# TopLevel.net
KiCad netlist of a schematic drawn in Altium Designer
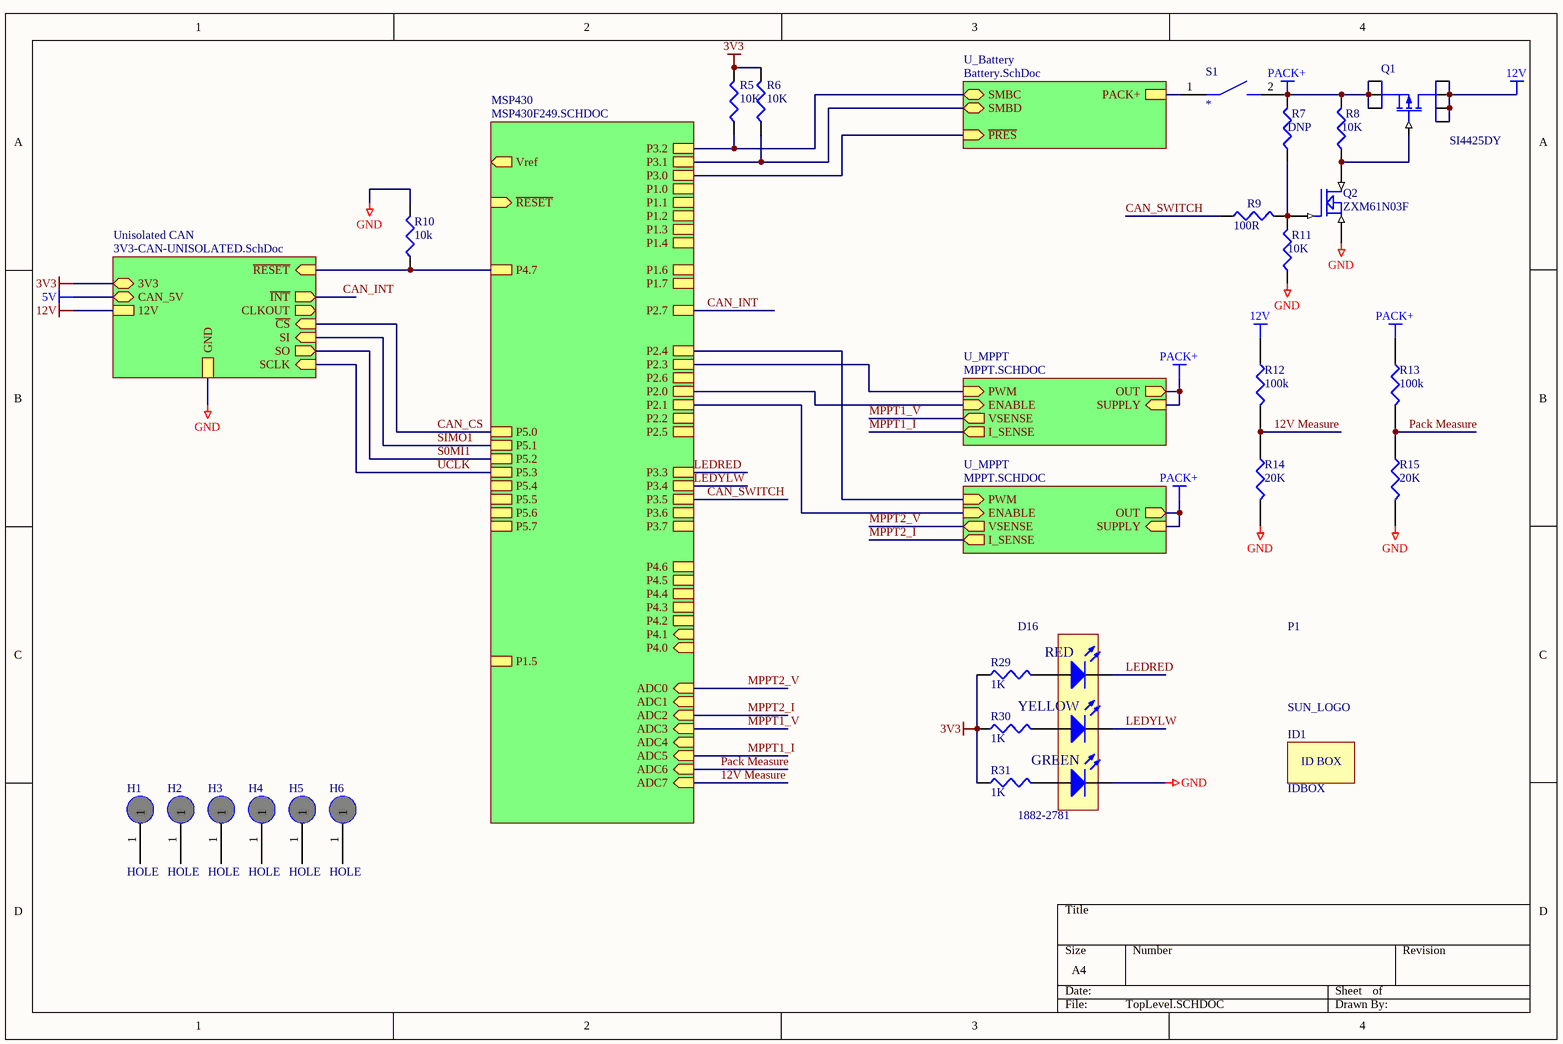
[diagram p0: TopLevel.SCHDOC]

(export (version "E")
  (design (tool "Eeschema 10.0.6"))
  (components
    (comp (ref "D16")
      (value "1882-2781")
      (footprint "LED_TRILEVEL")
      (description "Three level LED")
      (libsource (lib "RCLDQ") (part "LED-TRILEVEL"))
    )
    (comp (ref "H1")
      (value "HOLE")
      (footprint "M3")
      (description "Hole")
      (libsource (lib "Miscellaneous") (part "HOLE"))
    )
    (comp (ref "H2")
      (value "HOLE")
      (footprint "M3")
      (description "Hole")
      (libsource (lib "Miscellaneous") (part "HOLE"))
    )
    (comp (ref "H3")
      (value "HOLE")
      (footprint "M3")
      (description "Hole")
      (libsource (lib "Miscellaneous") (part "HOLE"))
    )
    (comp (ref "H4")
      (value "HOLE")
      (footprint "M3")
      (description "Hole")
      (libsource (lib "Miscellaneous") (part "HOLE"))
    )
    (comp (ref "H5")
      (value "HOLE")
      (footprint "M3")
      (description "Hole")
      (libsource (lib "Miscellaneous") (part "HOLE"))
    )
    (comp (ref "H6")
      (value "HOLE")
      (footprint "M3")
      (description "Hole")
      (libsource (lib "Miscellaneous") (part "HOLE"))
    )
    (comp (ref "ID1") (value "IDBOX") (footprint "IDBOX") (libsource (lib "Miscellaneous") (part "IDBOX")))
    (comp (ref "P1")
      (value "SUN_LOGO")
      (footprint "SUNSWIFTLOGO")
      (libsource (lib "Miscellaneous") (part "SUN_LOGO"))
    )
    (comp (ref "Q1")
      (value "SI4425DY")
      (footprint "SO8")
      (description "SI4425DY P Channel Mosfet")
      (libsource (lib "RCLDQ") (part "SI4425DY"))
    )
    (comp (ref "Q2")
      (value "ZXM61N03F")
      (footprint "SOT23(3)")
      (description "1.7A, 20V N-Channel Enhancement mode FET")
      (libsource (lib "RCLDQ") (part "ZXM61N02F"))
    )
    (comp (ref "R5")
      (value "10K")
      (footprint "0603")
      (description "Resistor")
      (libsource (lib "RCLDQ") (part "RES1"))
    )
    (comp (ref "R6")
      (value "10K")
      (footprint "0603")
      (description "Resistor")
      (libsource (lib "RCLDQ") (part "RES1"))
    )
    (comp (ref "R7")
      (value "DNP")
      (footprint "0603")
      (description "Resistor")
      (libsource (lib "*") (part "RES1"))
    )
    (comp (ref "R8")
      (value "10K")
      (footprint "0603")
      (description "Resistor")
      (libsource (lib "*") (part "RES1"))
    )
    (comp (ref "R9") (value "100R") (footprint "0603") (libsource (lib "RCLDQ") (part "RES1")))
    (comp (ref "R10")
      (value "10k")
      (footprint "0603")
      (description "Resistor")
      (libsource (lib "SunswiftLib20030312RR") (part "RES1"))
    )
    (comp (ref "R11")
      (value "10K")
      (footprint "0603")
      (description "Resistor")
      (libsource (lib "*") (part "RES1"))
    )
    (comp (ref "R12") (value "100k") (footprint "1206") (libsource (lib "") (part "RES1_1")))
    (comp (ref "R13") (value "100k") (footprint "1206") (libsource (lib "") (part "RES1_1")))
    (comp (ref "R14") (value "20K") (footprint "1206") (libsource (lib "") (part "RES1_1")))
    (comp (ref "R15") (value "20K") (footprint "1206") (libsource (lib "") (part "RES1_1")))
    (comp (ref "R29")
      (value "1K")
      (footprint "0603")
      (description "Resistor")
      (libsource (lib "RCLDQ") (part "RES1"))
    )
    (comp (ref "R30")
      (value "1K")
      (footprint "0603")
      (description "Resistor")
      (libsource (lib "RCLDQ") (part "RES1"))
    )
    (comp (ref "R31")
      (value "1K")
      (footprint "0603")
      (description "Resistor")
      (libsource (lib "RCLDQ") (part "RES1"))
    )
    (comp (ref "S1") (value "*") (libsource (lib "Miscellaneous") (part "SWITCH")))
  )
  (nets
    (net (code "1") (name "/12V Measure") (class "Default")
      (node (ref "R12") (pin "2") (pinfunction "2_2") (pintype "passive"))
      (node (ref "R14") (pin "1") (pinfunction "1_1") (pintype "passive"))
    )
    (net (code "6") (name "/CAN_SWITCH") (class "Default")
      (node (ref "R9") (pin "1") (pinfunction "1_1") (pintype "passive"))
    )
    (net (code "10") (name "/LEDRED") (class "Default")
      (node (ref "D16") (pin "3") (pinfunction "K_3") (pintype "passive"))
    )
    (net (code "11") (name "/LEDYLW") (class "Default")
      (node (ref "D16") (pin "2") (pinfunction "K_2") (pintype "passive"))
    )
    (net (code "30") (name "/P3.1") (class "Default")
      (node (ref "R6") (pin "1") (pinfunction "1_1") (pintype "passive"))
    )
    (net (code "31") (name "/P3.2") (class "Default")
      (node (ref "R5") (pin "1") (pinfunction "1_1") (pintype "passive"))
    )
    (net (code "41") (name "/P4.7") (class "Default")
      (node (ref "R10") (pin "1") (pinfunction "1_1") (pintype "passive"))
    )
    (net (code "46") (name "/PACK+") (class "Default")
      (node (ref "S1") (pin "1") (pinfunction "1_1") (pintype "passive"))
    )
    (net (code "47") (name "/Pack Measure") (class "Default")
      (node (ref "R13") (pin "2") (pinfunction "2_2") (pintype "passive"))
      (node (ref "R15") (pin "1") (pinfunction "1_1") (pintype "passive"))
    )
    (net (code "53") (name "3V3") (class "Default")
      (node (ref "R29") (pin "1") (pinfunction "1_1") (pintype "passive"))
      (node (ref "R30") (pin "1") (pinfunction "1_1") (pintype "passive"))
      (node (ref "R31") (pin "1") (pinfunction "1_1") (pintype "passive"))
      (node (ref "R5") (pin "2") (pinfunction "2_2") (pintype "passive"))
      (node (ref "R6") (pin "2") (pinfunction "2_2") (pintype "passive"))
    )
    (net (code "55") (name "12V") (class "Default")
      (node (ref "Q1") (pin "5") (pinfunction "D_5") (pintype "bidirectional"))
      (node (ref "Q1") (pin "6") (pinfunction "D_6") (pintype "bidirectional"))
      (node (ref "Q1") (pin "7") (pinfunction "D_7") (pintype "bidirectional"))
      (node (ref "Q1") (pin "8") (pinfunction "D_8") (pintype "bidirectional"))
      (node (ref "R12") (pin "1") (pinfunction "1_1") (pintype "passive"))
    )
    (net (code "56") (name "GND") (class "Default")
      (node (ref "D16") (pin "1") (pinfunction "K_1") (pintype "passive"))
      (node (ref "Q2") (pin "2") (pinfunction "S_2") (pintype "input"))
      (node (ref "R10") (pin "2") (pinfunction "2_2") (pintype "passive"))
      (node (ref "R11") (pin "1") (pinfunction "1_1") (pintype "passive"))
      (node (ref "R14") (pin "2") (pinfunction "2_2") (pintype "passive"))
      (node (ref "R15") (pin "2") (pinfunction "2_2") (pintype "passive"))
    )
    (net (code "57") (name "Net-(D16-A-Pad4)") (class "Default")
      (node (ref "D16") (pin "4") (pinfunction "A_4") (pintype "passive"))
      (node (ref "R29") (pin "2") (pinfunction "2_2") (pintype "passive"))
    )
    (net (code "58") (name "Net-(D16-A-Pad5)") (class "Default")
      (node (ref "D16") (pin "5") (pinfunction "A_5") (pintype "passive"))
      (node (ref "R30") (pin "2") (pinfunction "2_2") (pintype "passive"))
    )
    (net (code "59") (name "Net-(D16-A-Pad6)") (class "Default")
      (node (ref "D16") (pin "6") (pinfunction "A_6") (pintype "passive"))
      (node (ref "R31") (pin "2") (pinfunction "2_2") (pintype "passive"))
    )
    (net (code "60") (name "Net-(Q1-G)") (class "Default")
      (node (ref "Q1") (pin "4") (pinfunction "G_4") (pintype "input"))
      (node (ref "Q2") (pin "3") (pinfunction "D_3") (pintype "input"))
      (node (ref "R8") (pin "1") (pinfunction "1_1") (pintype "passive"))
    )
    (net (code "61") (name "Net-(Q2-G)") (class "Default")
      (node (ref "Q2") (pin "1") (pinfunction "G_1") (pintype "input"))
      (node (ref "R11") (pin "2") (pinfunction "2_2") (pintype "passive"))
      (node (ref "R7") (pin "1") (pinfunction "1_1") (pintype "passive"))
      (node (ref "R9") (pin "2") (pinfunction "2_2") (pintype "passive"))
    )
    (net (code "62") (name "PACK+") (class "Default")
      (node (ref "Q1") (pin "1") (pinfunction "S_1") (pintype "bidirectional"))
      (node (ref "Q1") (pin "2") (pinfunction "S_2") (pintype "bidirectional"))
      (node (ref "Q1") (pin "3") (pinfunction "S_3") (pintype "bidirectional"))
      (node (ref "R13") (pin "1") (pinfunction "1_1") (pintype "passive"))
      (node (ref "R7") (pin "2") (pinfunction "2_2") (pintype "passive"))
      (node (ref "R8") (pin "2") (pinfunction "2_2") (pintype "passive"))
      (node (ref "S1") (pin "2") (pinfunction "2_2") (pintype "passive"))
    )
    (net (code "63") (name "unconnected-(H1-Pad1)") (class "Default")
      (node (ref "H1") (pin "1") (pinfunction "1_1") (pintype "passive"))
    )
    (net (code "64") (name "unconnected-(H2-Pad1)") (class "Default")
      (node (ref "H2") (pin "1") (pinfunction "1_1") (pintype "passive"))
    )
    (net (code "65") (name "unconnected-(H3-Pad1)") (class "Default")
      (node (ref "H3") (pin "1") (pinfunction "1_1") (pintype "passive"))
    )
    (net (code "66") (name "unconnected-(H4-Pad1)") (class "Default")
      (node (ref "H4") (pin "1") (pinfunction "1_1") (pintype "passive"))
    )
    (net (code "67") (name "unconnected-(H5-Pad1)") (class "Default")
      (node (ref "H5") (pin "1") (pinfunction "1_1") (pintype "passive"))
    )
    (net (code "68") (name "unconnected-(H6-Pad1)") (class "Default")
      (node (ref "H6") (pin "1") (pinfunction "1_1") (pintype "passive"))
    )
  )
)
